# Arduino-TPUART.net
KiCad netlist of a schematic drawn in EAGLE
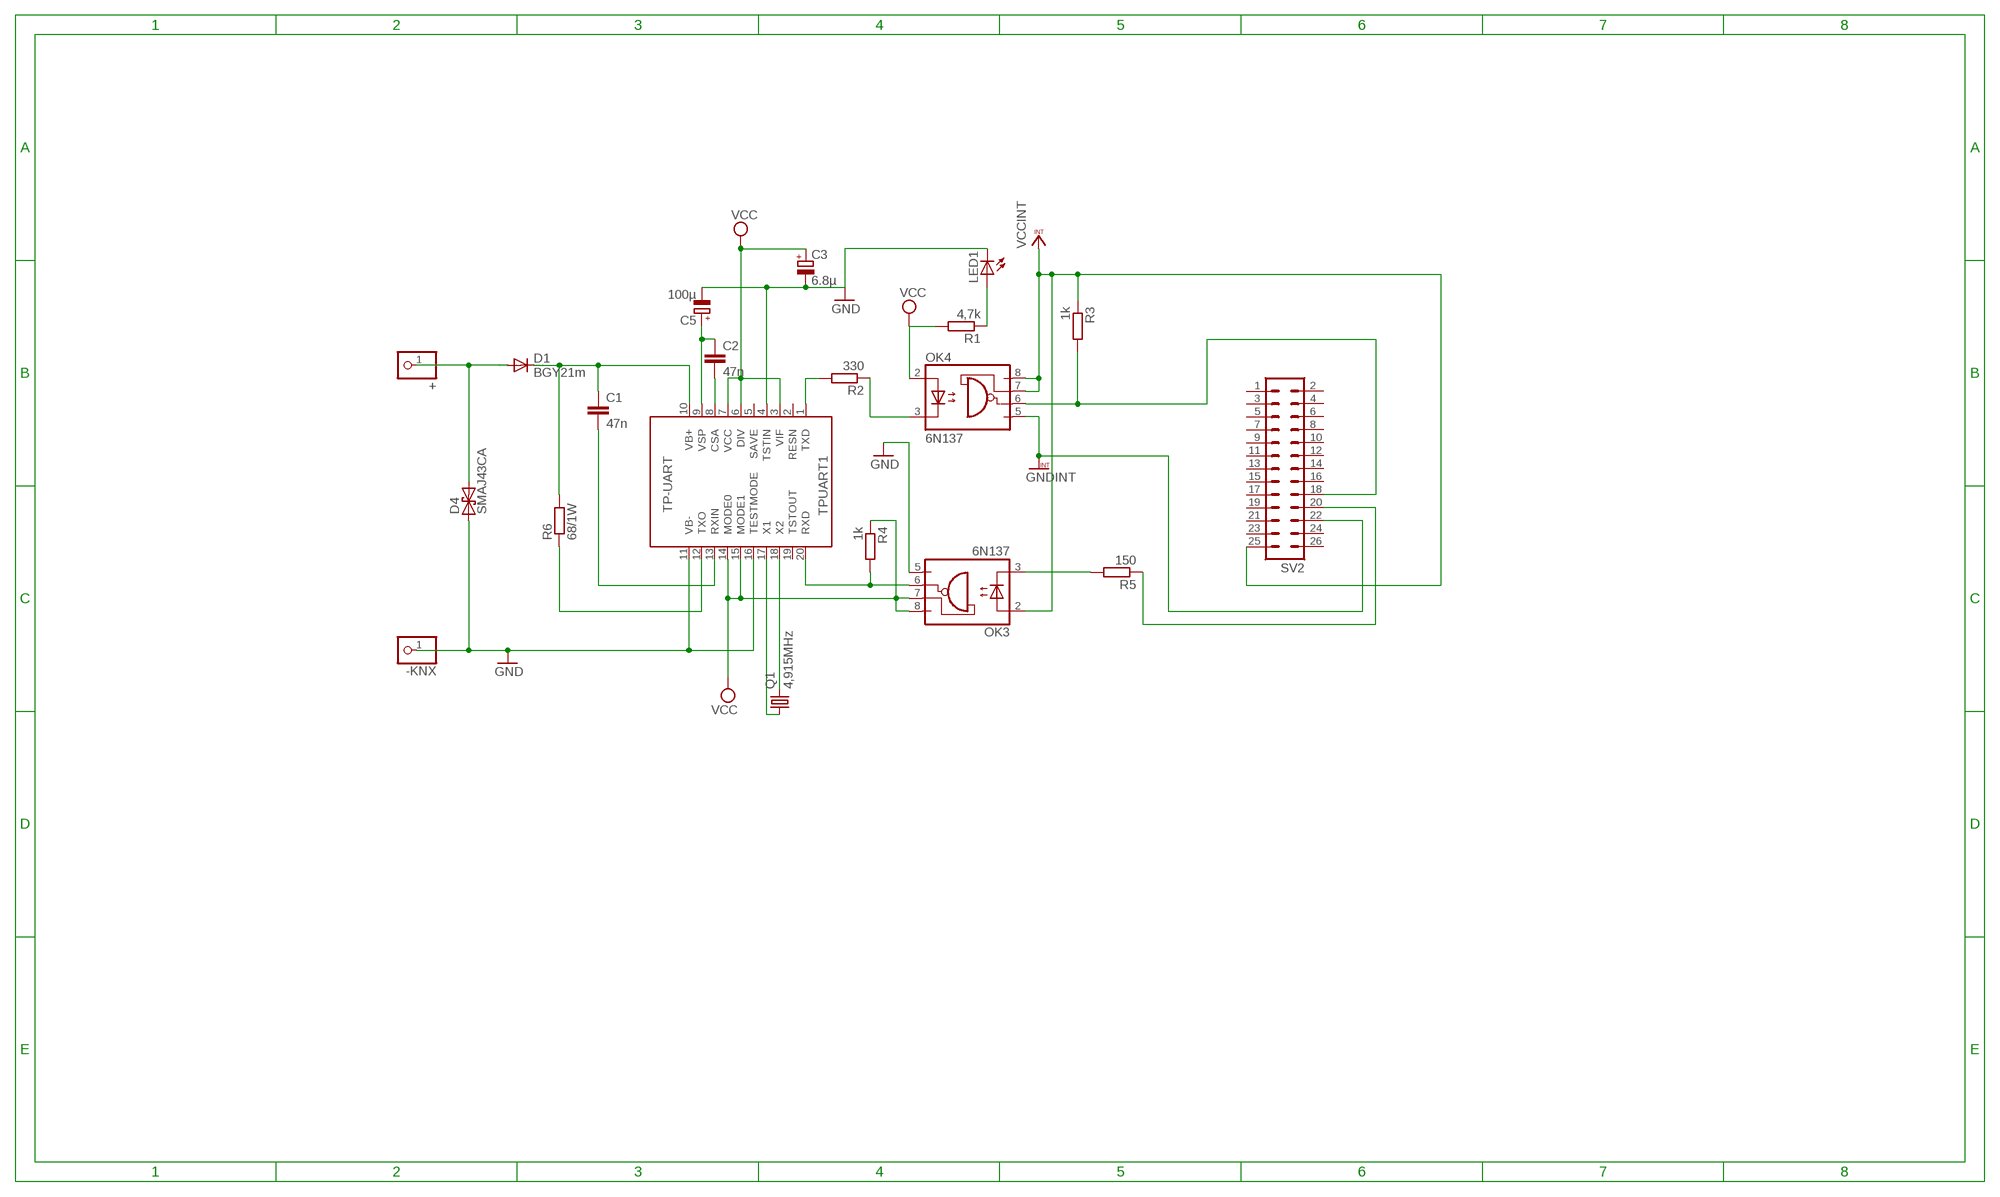
[diagram p0: schematic, sheet 1]

(export (version "E")
  (design (tool "Eeschema 10.0.6"))
  (components
    (comp (ref "+")
      (value "PINHD-1X1")
      (footprint "eagle-import:1X01")
      (libsource (lib "eagle-import") (part "PINHD-1X1"))
    )
    (comp (ref "-KNX")
      (value "PINHD-1X1")
      (footprint "eagle-import:1X01")
      (libsource (lib "eagle-import") (part "PINHD-1X1"))
    )
    (comp (ref "C1")
      (value "47n")
      (footprint "eagle-import:C1206")
      (libsource (lib "eagle-import") (part "C-EUC1206"))
    )
    (comp (ref "C2")
      (value "47n")
      (footprint "eagle-import:C1206")
      (libsource (lib "eagle-import") (part "C-EUC1206"))
    )
    (comp (ref "C3")
      (value "6.8µ")
      (footprint "eagle-import:CT7343")
      (libsource (lib "eagle-import") (part "CPOL-EUCT7343"))
    )
    (comp (ref "C5")
      (value "100µ")
      (footprint "eagle-import:CT7343")
      (libsource (lib "eagle-import") (part "CPOL-EUCT7343"))
    )
    (comp (ref "D1")
      (value "BGY21m")
      (footprint "eagle-import:SMB")
      (libsource (lib "eagle-import") (part "ES2D"))
    )
    (comp (ref "D4")
      (value "SMAJ43CA")
      (footprint "eagle-import:DO214AA")
      (libsource (lib "eagle-import") (part "BZW04XXB"))
    )
    (comp (ref "LED1")
      (value "LEDKA-3528ASYC")
      (footprint "eagle-import:KA-3528ASYC")
      (libsource (lib "eagle-import") (part "LEDKA-3528ASYC"))
    )
    (comp (ref "OK3")
      (value "6N137")
      (footprint "eagle-import:DIL8-SMD")
      (libsource (lib "eagle-import") (part "6N137"))
    )
    (comp (ref "OK4")
      (value "6N137")
      (footprint "eagle-import:DIL8-SMD")
      (libsource (lib "eagle-import") (part "6N137"))
    )
    (comp (ref "Q1")
      (value "4,915MHz")
      (footprint "eagle-import:HC49UP")
      (libsource (lib "eagle-import") (part "CRYSTALHC49UP"))
    )
    (comp (ref "R1")
      (value "4,7k")
      (footprint "eagle-import:M1206")
      (libsource (lib "eagle-import") (part "R-EU_M1206"))
    )
    (comp (ref "R2")
      (value "330")
      (footprint "eagle-import:M1206")
      (libsource (lib "eagle-import") (part "R-EU_M1206"))
    )
    (comp (ref "R3")
      (value "1k")
      (footprint "eagle-import:M1206")
      (libsource (lib "eagle-import") (part "R-EU_M1206"))
    )
    (comp (ref "R4")
      (value "1k")
      (footprint "eagle-import:M1206")
      (libsource (lib "eagle-import") (part "R-EU_M1206"))
    )
    (comp (ref "R5")
      (value "150")
      (footprint "eagle-import:M1206")
      (libsource (lib "eagle-import") (part "R-EU_M1206"))
    )
    (comp (ref "R6")
      (value "68/1W")
      (footprint "eagle-import:R2512")
      (libsource (lib "eagle-import") (part "R-EU_R2512"))
    )
    (comp (ref "SV2")
      (value "MA13-2")
      (footprint "eagle-import:MA13-2")
      (libsource (lib "eagle-import") (part "MA13-2"))
    )
    (comp (ref "TPUART1")
      (value "TP-UART")
      (footprint "eagle-import:SOIC20")
      (libsource (lib "eagle-import") (part "TP-UART"))
    )
  )
  (nets
    (net (code "1") (name "GND") (class "Default")
      (node (ref "-KNX") (pin "1") (pinfunction "1_1") (pintype "passive"))
      (node (ref "C3") (pin "-") (pinfunction "-_-") (pintype "passive"))
      (node (ref "C5") (pin "-") (pinfunction "-_-") (pintype "passive"))
      (node (ref "D4") (pin "A") (pinfunction "1_A") (pintype "passive"))
      (node (ref "LED1") (pin "C") (pinfunction "C_C") (pintype "passive"))
      (node (ref "OK3") (pin "5") (pinfunction "GND_5") (pintype "passive"))
      (node (ref "TPUART1") (pin "11") (pinfunction "VB-_11") (pintype "passive"))
      (node (ref "TPUART1") (pin "16") (pinfunction "TESTMODE_16") (pintype "input"))
      (node (ref "TPUART1") (pin "4") (pinfunction "TSTIN_4") (pintype "bidirectional"))
    )
    (net (code "2") (name "GNDINT") (class "Default")
      (node (ref "OK4") (pin "5") (pinfunction "GND_5") (pintype "passive"))
      (node (ref "SV2") (pin "22") (pinfunction "22_22") (pintype "passive"))
    )
    (net (code "3") (name "Net-(D4-2)") (class "Default")
      (node (ref "+") (pin "1") (pinfunction "1_1") (pintype "passive"))
      (node (ref "D1") (pin "A") (pinfunction "A_A") (pintype "passive"))
      (node (ref "D4") (pin "C") (pinfunction "2_C") (pintype "passive"))
    )
    (net (code "4") (name "Net-(LED1-PadA)") (class "Default")
      (node (ref "LED1") (pin "A") (pinfunction "A_A") (pintype "passive"))
      (node (ref "R1") (pin "1") (pinfunction "1_1") (pintype "passive"))
    )
    (net (code "5") (name "Net-(OK3-C)") (class "Default")
      (node (ref "OK3") (pin "3") (pinfunction "C_3") (pintype "passive"))
      (node (ref "R5") (pin "2") (pinfunction "2_2") (pintype "passive"))
    )
    (net (code "6") (name "Net-(OK3-VO)") (class "Default")
      (node (ref "OK3") (pin "6") (pinfunction "VO_6") (pintype "passive"))
      (node (ref "R4") (pin "2") (pinfunction "2_2") (pintype "passive"))
      (node (ref "TPUART1") (pin "20") (pinfunction "RXD_20") (pintype "input"))
    )
    (net (code "7") (name "Net-(OK4-C)") (class "Default")
      (node (ref "OK4") (pin "3") (pinfunction "C_3") (pintype "passive"))
      (node (ref "R2") (pin "1") (pinfunction "1_1") (pintype "passive"))
    )
    (net (code "8") (name "Net-(OK4-VO)") (class "Default")
      (node (ref "OK4") (pin "6") (pinfunction "VO_6") (pintype "passive"))
      (node (ref "R3") (pin "2") (pinfunction "2_2") (pintype "passive"))
      (node (ref "SV2") (pin "18") (pinfunction "18_18") (pintype "passive"))
    )
    (net (code "9") (name "Net-(R5-Pad1)") (class "Default")
      (node (ref "R5") (pin "1") (pinfunction "1_1") (pintype "passive"))
      (node (ref "SV2") (pin "20") (pinfunction "20_20") (pintype "passive"))
    )
    (net (code "10") (name "Net-(TPUART1-CSA)") (class "Default")
      (node (ref "C2") (pin "2") (pinfunction "2_2") (pintype "passive"))
      (node (ref "TPUART1") (pin "8") (pinfunction "CSA_8") (pintype "passive"))
    )
    (net (code "11") (name "Net-(TPUART1-RXIN)") (class "Default")
      (node (ref "C1") (pin "2") (pinfunction "2_2") (pintype "passive"))
      (node (ref "TPUART1") (pin "13") (pinfunction "RXIN_13") (pintype "input"))
    )
    (net (code "12") (name "Net-(TPUART1-TXD)") (class "Default")
      (node (ref "R2") (pin "2") (pinfunction "2_2") (pintype "passive"))
      (node (ref "TPUART1") (pin "1") (pinfunction "TXD_1") (pintype "output"))
    )
    (net (code "13") (name "Net-(TPUART1-TXO)") (class "Default")
      (node (ref "R6") (pin "1") (pinfunction "1_1") (pintype "passive"))
      (node (ref "TPUART1") (pin "12") (pinfunction "TXO_12") (pintype "output"))
    )
    (net (code "14") (name "Net-(TPUART1-VB+)") (class "Default")
      (node (ref "C1") (pin "1") (pinfunction "1_1") (pintype "passive"))
      (node (ref "D1") (pin "C") (pinfunction "C_C") (pintype "passive"))
      (node (ref "R6") (pin "2") (pinfunction "2_2") (pintype "passive"))
      (node (ref "TPUART1") (pin "10") (pinfunction "VB+_10") (pintype "passive"))
    )
    (net (code "15") (name "Net-(TPUART1-VSP)") (class "Default")
      (node (ref "C2") (pin "1") (pinfunction "1_1") (pintype "passive"))
      (node (ref "C5") (pin "+") (pinfunction "+_+") (pintype "passive"))
      (node (ref "TPUART1") (pin "9") (pinfunction "VSP_9") (pintype "passive"))
    )
    (net (code "16") (name "Net-(TPUART1-X1)") (class "Default")
      (node (ref "Q1") (pin "1") (pinfunction "1_1") (pintype "passive"))
      (node (ref "TPUART1") (pin "17") (pinfunction "X1_17") (pintype "passive"))
    )
    (net (code "17") (name "Net-(TPUART1-X2)") (class "Default")
      (node (ref "Q1") (pin "2") (pinfunction "2_2") (pintype "passive"))
      (node (ref "TPUART1") (pin "18") (pinfunction "X2_18") (pintype "passive"))
    )
    (net (code "18") (name "VCC") (class "Default")
      (node (ref "C3") (pin "+") (pinfunction "+_+") (pintype "passive"))
      (node (ref "OK3") (pin "7") (pinfunction "VE_7") (pintype "passive"))
      (node (ref "OK3") (pin "8") (pinfunction "VCC_8") (pintype "passive"))
      (node (ref "OK4") (pin "2") (pinfunction "A_2") (pintype "passive"))
      (node (ref "R1") (pin "2") (pinfunction "2_2") (pintype "passive"))
      (node (ref "R4") (pin "1") (pinfunction "1_1") (pintype "passive"))
      (node (ref "TPUART1") (pin "14") (pinfunction "MODE0_14") (pintype "input"))
      (node (ref "TPUART1") (pin "15") (pinfunction "MODE1_15") (pintype "input"))
      (node (ref "TPUART1") (pin "3") (pinfunction "VIF_3") (pintype "input"))
      (node (ref "TPUART1") (pin "6") (pinfunction "DIV_6") (pintype "input"))
      (node (ref "TPUART1") (pin "7") (pinfunction "VCC_7") (pintype "output"))
    )
    (net (code "19") (name "VCCINT") (class "Default")
      (node (ref "OK3") (pin "2") (pinfunction "A_2") (pintype "passive"))
      (node (ref "OK4") (pin "7") (pinfunction "VE_7") (pintype "passive"))
      (node (ref "OK4") (pin "8") (pinfunction "VCC_8") (pintype "passive"))
      (node (ref "R3") (pin "1") (pinfunction "1_1") (pintype "passive"))
      (node (ref "SV2") (pin "25") (pinfunction "25_25") (pintype "passive"))
    )
    (net (code "20") (name "unconnected-(SV2-Pad1)") (class "Default")
      (node (ref "SV2") (pin "1") (pinfunction "1_1") (pintype "passive"))
    )
    (net (code "21") (name "unconnected-(SV2-Pad2)") (class "Default")
      (node (ref "SV2") (pin "2") (pinfunction "2_2") (pintype "passive"))
    )
    (net (code "22") (name "unconnected-(SV2-Pad3)") (class "Default")
      (node (ref "SV2") (pin "3") (pinfunction "3_3") (pintype "passive"))
    )
    (net (code "23") (name "unconnected-(SV2-Pad4)") (class "Default")
      (node (ref "SV2") (pin "4") (pinfunction "4_4") (pintype "passive"))
    )
    (net (code "24") (name "unconnected-(SV2-Pad5)") (class "Default")
      (node (ref "SV2") (pin "5") (pinfunction "5_5") (pintype "passive"))
    )
    (net (code "25") (name "unconnected-(SV2-Pad6)") (class "Default")
      (node (ref "SV2") (pin "6") (pinfunction "6_6") (pintype "passive"))
    )
    (net (code "26") (name "unconnected-(SV2-Pad7)") (class "Default")
      (node (ref "SV2") (pin "7") (pinfunction "7_7") (pintype "passive"))
    )
    (net (code "27") (name "unconnected-(SV2-Pad8)") (class "Default")
      (node (ref "SV2") (pin "8") (pinfunction "8_8") (pintype "passive"))
    )
    (net (code "28") (name "unconnected-(SV2-Pad9)") (class "Default")
      (node (ref "SV2") (pin "9") (pinfunction "9_9") (pintype "passive"))
    )
    (net (code "29") (name "unconnected-(SV2-Pad10)") (class "Default")
      (node (ref "SV2") (pin "10") (pinfunction "10_10") (pintype "passive"))
    )
    (net (code "30") (name "unconnected-(SV2-Pad11)") (class "Default")
      (node (ref "SV2") (pin "11") (pinfunction "11_11") (pintype "passive"))
    )
    (net (code "31") (name "unconnected-(SV2-Pad12)") (class "Default")
      (node (ref "SV2") (pin "12") (pinfunction "12_12") (pintype "passive"))
    )
    (net (code "32") (name "unconnected-(SV2-Pad13)") (class "Default")
      (node (ref "SV2") (pin "13") (pinfunction "13_13") (pintype "passive"))
    )
    (net (code "33") (name "unconnected-(SV2-Pad14)") (class "Default")
      (node (ref "SV2") (pin "14") (pinfunction "14_14") (pintype "passive"))
    )
    (net (code "34") (name "unconnected-(SV2-Pad15)") (class "Default")
      (node (ref "SV2") (pin "15") (pinfunction "15_15") (pintype "passive"))
    )
    (net (code "35") (name "unconnected-(SV2-Pad16)") (class "Default")
      (node (ref "SV2") (pin "16") (pinfunction "16_16") (pintype "passive"))
    )
    (net (code "36") (name "unconnected-(SV2-Pad17)") (class "Default")
      (node (ref "SV2") (pin "17") (pinfunction "17_17") (pintype "passive"))
    )
    (net (code "37") (name "unconnected-(SV2-Pad19)") (class "Default")
      (node (ref "SV2") (pin "19") (pinfunction "19_19") (pintype "passive"))
    )
    (net (code "38") (name "unconnected-(SV2-Pad21)") (class "Default")
      (node (ref "SV2") (pin "21") (pinfunction "21_21") (pintype "passive"))
    )
    (net (code "39") (name "unconnected-(SV2-Pad23)") (class "Default")
      (node (ref "SV2") (pin "23") (pinfunction "23_23") (pintype "passive"))
    )
    (net (code "40") (name "unconnected-(SV2-Pad24)") (class "Default")
      (node (ref "SV2") (pin "24") (pinfunction "24_24") (pintype "passive"))
    )
    (net (code "41") (name "unconnected-(SV2-Pad26)") (class "Default")
      (node (ref "SV2") (pin "26") (pinfunction "26_26") (pintype "passive"))
    )
    (net (code "42") (name "unconnected-(TPUART1-RESN-Pad2)") (class "Default")
      (node (ref "TPUART1") (pin "2") (pinfunction "RESN_2") (pintype "bidirectional"))
    )
    (net (code "43") (name "unconnected-(TPUART1-SAVE-Pad5)") (class "Default")
      (node (ref "TPUART1") (pin "5") (pinfunction "SAVE_5") (pintype "open_collector"))
    )
    (net (code "44") (name "unconnected-(TPUART1-TSTOUT-Pad19)") (class "Default")
      (node (ref "TPUART1") (pin "19") (pinfunction "TSTOUT_19") (pintype "output"))
    )
  )
)
